# LPF-8-Order.net
KiCad netlist of a schematic drawn in Altium Designer
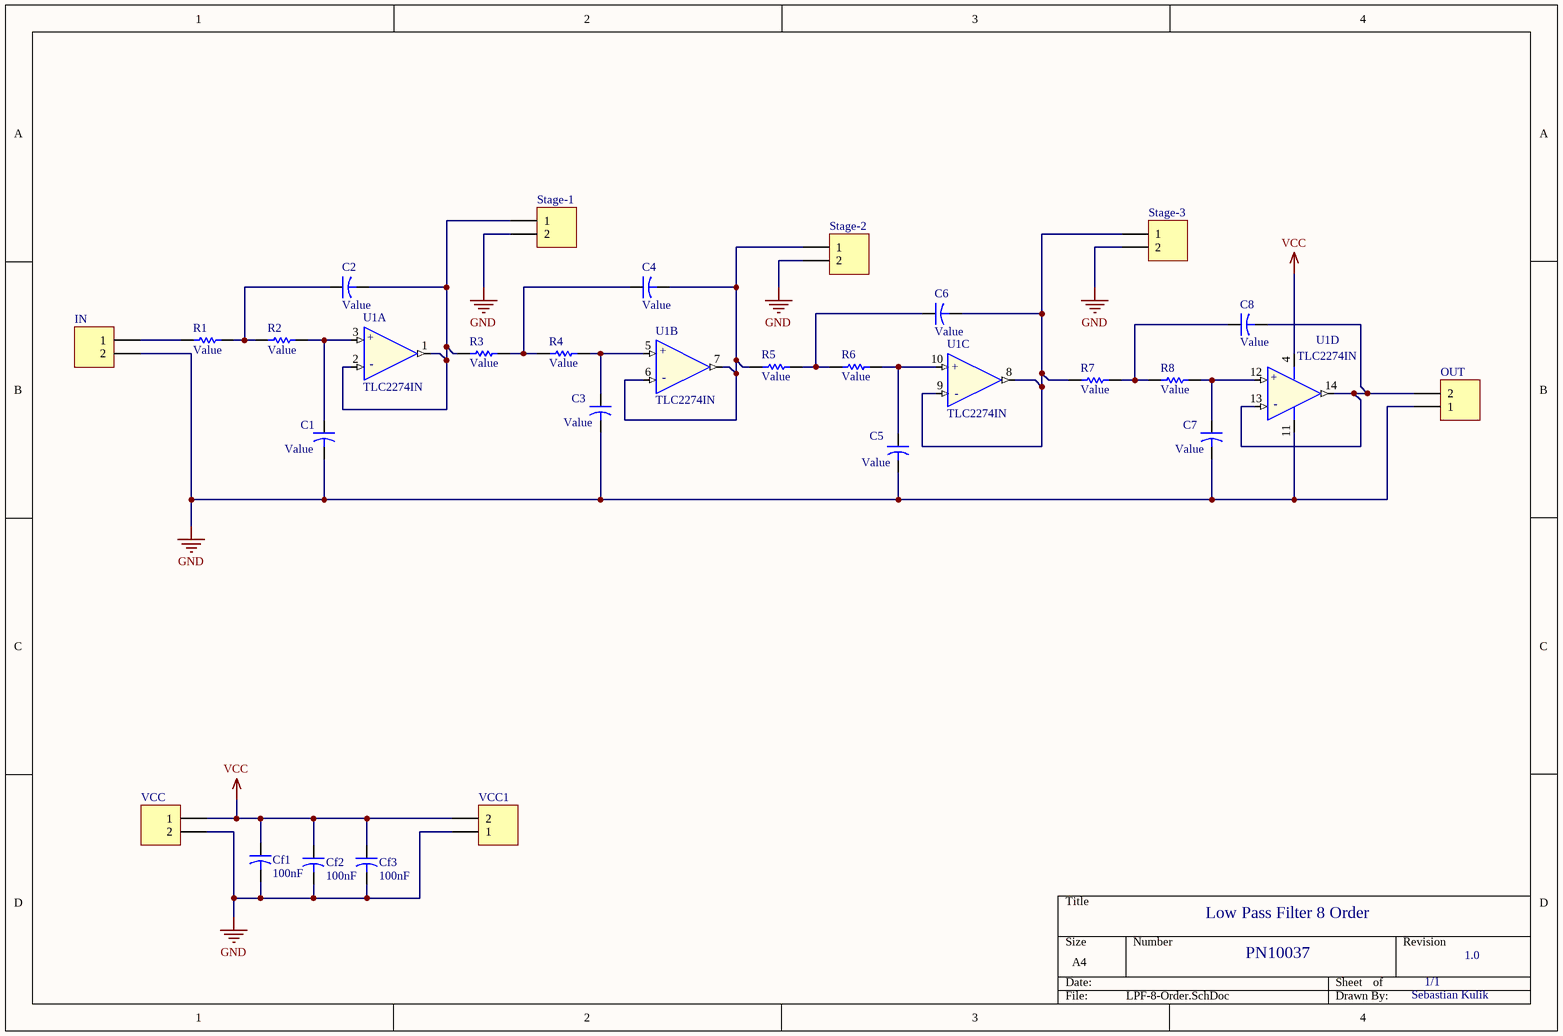
[diagram p0: LPF-8-Order.SchDoc]

(export (version "E")
  (design (tool "Eeschema 10.0.6"))
  (components
    (comp (ref "C1")
      (value "Value")
      (footprint "Dummy-10mm")
      (description "Capacitor-Dummy-THT")
      (fields (field (name "PUBLISHER") "Sebastian Kulik"))
      (libsource (lib "Capacitors") (part "Capacitor-Dummy-THT"))
    )
    (comp (ref "C2")
      (value "Value")
      (footprint "Dummy-10mm")
      (description "Capacitor-Dummy-THT")
      (fields (field (name "PUBLISHER") "Sebastian Kulik"))
      (libsource (lib "Capacitors") (part "Capacitor-Dummy-THT"))
    )
    (comp (ref "C3")
      (value "Value")
      (footprint "Dummy-10mm")
      (description "Capacitor-Dummy-THT")
      (fields (field (name "PUBLISHER") "Sebastian Kulik"))
      (libsource (lib "Capacitors") (part "Capacitor-Dummy-THT"))
    )
    (comp (ref "C4")
      (value "Value")
      (footprint "Dummy-10mm")
      (description "Capacitor-Dummy-THT")
      (fields (field (name "PUBLISHER") "Sebastian Kulik"))
      (libsource (lib "Capacitors") (part "Capacitor-Dummy-THT"))
    )
    (comp (ref "C5")
      (value "Value")
      (footprint "Dummy-10mm")
      (description "Capacitor-Dummy-THT")
      (fields (field (name "PUBLISHER") "Sebastian Kulik"))
      (libsource (lib "Capacitors") (part "Capacitor-Dummy-THT"))
    )
    (comp (ref "C6")
      (value "Value")
      (footprint "Dummy-10mm")
      (description "Capacitor-Dummy-THT")
      (fields (field (name "PUBLISHER") "Sebastian Kulik"))
      (libsource (lib "Capacitors") (part "Capacitor-Dummy-THT"))
    )
    (comp (ref "C7")
      (value "Value")
      (footprint "Dummy-10mm")
      (description "Capacitor-Dummy-THT")
      (fields (field (name "PUBLISHER") "Sebastian Kulik"))
      (libsource (lib "Capacitors") (part "Capacitor-Dummy-THT"))
    )
    (comp (ref "C8")
      (value "Value")
      (footprint "Dummy-10mm")
      (description "Capacitor-Dummy-THT")
      (fields (field (name "PUBLISHER") "Sebastian Kulik"))
      (libsource (lib "Capacitors") (part "Capacitor-Dummy-THT"))
    )
    (comp (ref "Cf1")
      (value "100nF")
      (footprint "Dummy-10mm")
      (description "Capacitor-Dummy-THT")
      (fields (field (name "PUBLISHER") "Sebastian Kulik"))
      (libsource (lib "Capacitors") (part "Capacitor-Dummy-THT"))
    )
    (comp (ref "Cf2")
      (value "100nF")
      (footprint "Dummy-10mm")
      (description "Capacitor-Dummy-THT")
      (fields (field (name "PUBLISHER") "Sebastian Kulik"))
      (libsource (lib "Capacitors") (part "Capacitor-Dummy-THT"))
    )
    (comp (ref "Cf3")
      (value "100nF")
      (footprint "Dummy-10mm")
      (description "Capacitor-Dummy-THT")
      (fields (field (name "PUBLISHER") "Sebastian Kulik"))
      (libsource (lib "Capacitors") (part "Capacitor-Dummy-THT"))
    )
    (comp (ref "IN")
      (value "PHOENIX_1715721")
      (footprint "Phoenix-2-5_08")
      (description "Phoenix, 2 pol, 5.08mm, 22A, 715721")
      (fields (field (name "MANUFACTURER") "Phoenix") (field (name "PUBLISHER") "Sebastian Kulik"))
      (libsource (lib "") (part "2Pol_1715721_1"))
    )
    (comp (ref "OUT")
      (value "PHOENIX_1715721")
      (footprint "Phoenix-2-5_08")
      (description "Phoenix, 2 pol, 5.08mm, 22A, 715721")
      (fields (field (name "MANUFACTURER") "Phoenix") (field (name "PUBLISHER") "Sebastian Kulik"))
      (libsource (lib "Connectors") (part "2Pol_1715721"))
    )
    (comp (ref "R1")
      (value "Value")
      (footprint "Dummy-10mm")
      (description "Resistor-Dummy-THT")
      (fields (field (name "PUBLISHER") "Sebastian Kulik"))
      (libsource (lib "Resistors") (part "Resistor-Dummy-THT"))
    )
    (comp (ref "R2")
      (value "Value")
      (footprint "Dummy-10mm")
      (description "Resistor-Dummy-THT")
      (fields (field (name "PUBLISHER") "Sebastian Kulik"))
      (libsource (lib "Resistors") (part "Resistor-Dummy-THT"))
    )
    (comp (ref "R3")
      (value "Value")
      (footprint "Dummy-10mm")
      (description "Resistor-Dummy-THT")
      (fields (field (name "PUBLISHER") "Sebastian Kulik"))
      (libsource (lib "Resistors") (part "Resistor-Dummy-THT"))
    )
    (comp (ref "R4")
      (value "Value")
      (footprint "Dummy-10mm")
      (description "Resistor-Dummy-THT")
      (fields (field (name "PUBLISHER") "Sebastian Kulik"))
      (libsource (lib "Resistors") (part "Resistor-Dummy-THT"))
    )
    (comp (ref "R5")
      (value "Value")
      (footprint "Dummy-10mm")
      (description "Resistor-Dummy-THT")
      (fields (field (name "PUBLISHER") "Sebastian Kulik"))
      (libsource (lib "Resistors") (part "Resistor-Dummy-THT"))
    )
    (comp (ref "R6")
      (value "Value")
      (footprint "Dummy-10mm")
      (description "Resistor-Dummy-THT")
      (fields (field (name "PUBLISHER") "Sebastian Kulik"))
      (libsource (lib "Resistors") (part "Resistor-Dummy-THT"))
    )
    (comp (ref "R7")
      (value "Value")
      (footprint "Dummy-10mm")
      (description "Resistor-Dummy-THT")
      (fields (field (name "PUBLISHER") "Sebastian Kulik"))
      (libsource (lib "Resistors") (part "Resistor-Dummy-THT"))
    )
    (comp (ref "R8")
      (value "Value")
      (footprint "Dummy-10mm")
      (description "Resistor-Dummy-THT")
      (fields (field (name "PUBLISHER") "Sebastian Kulik"))
      (libsource (lib "Resistors") (part "Resistor-Dummy-THT"))
    )
    (comp (ref "Stage-1")
      (value "Plug_2_90_2.54")
      (footprint "HDR1X2")
      (description "Plug, 2-Pin")
      (fields (field (name "MANUFACTURER") "WE") (field (name "PUBLISHER") "Sebastian Kulik"))
      (libsource (lib "Connectors") (part "Plug_2_90_2.54"))
    )
    (comp (ref "Stage-2")
      (value "Plug_2_90_2.54")
      (footprint "HDR1X2")
      (description "Plug, 2-Pin")
      (fields (field (name "MANUFACTURER") "WE") (field (name "PUBLISHER") "Sebastian Kulik"))
      (libsource (lib "Connectors") (part "Plug_2_90_2.54"))
    )
    (comp (ref "Stage-3")
      (value "Plug_2_90_2.54")
      (footprint "HDR1X2")
      (description "Plug, 2-Pin")
      (fields (field (name "MANUFACTURER") "WE") (field (name "PUBLISHER") "Sebastian Kulik"))
      (libsource (lib "Connectors") (part "Plug_2_90_2.54"))
    )
    (comp (ref "U1")
      (value "TLC2274IN")
      (footprint "DIP-14")
      (description "Reel to Reel  quad OP")
      (fields (field (name "MANUFACTURER") "TI") (field (name "PUBLISHER") "Sebastian Kulik"))
      (libsource (lib "") (part "TLC2274IN_1"))
    )
    (comp (ref "VCC")
      (value "PHOENIX_1715721")
      (footprint "Phoenix-2-5_08")
      (description "Phoenix, 2 pol, 5.08mm, 22A, 715721")
      (fields (field (name "MANUFACTURER") "Phoenix") (field (name "PUBLISHER") "Sebastian Kulik"))
      (libsource (lib "") (part "2Pol_1715721_1"))
    )
    (comp (ref "VCC1")
      (value "PHOENIX_1715721")
      (footprint "Phoenix-2-5_08")
      (description "Phoenix, 2 pol, 5.08mm, 22A, 715721")
      (fields (field (name "MANUFACTURER") "Phoenix") (field (name "PUBLISHER") "Sebastian Kulik"))
      (libsource (lib "Connectors") (part "2Pol_1715721"))
    )
  )
  (nets
    (net (code "1") (name "GND") (class "Default")
      (node (ref "C1") (pin "2") (pinfunction "2_2") (pintype "passive"))
      (node (ref "C3") (pin "2") (pinfunction "2_2") (pintype "passive"))
      (node (ref "C5") (pin "2") (pinfunction "2_2") (pintype "passive"))
      (node (ref "C7") (pin "2") (pinfunction "2_2") (pintype "passive"))
      (node (ref "Cf1") (pin "2") (pinfunction "2_2") (pintype "passive"))
      (node (ref "Cf2") (pin "2") (pinfunction "2_2") (pintype "passive"))
      (node (ref "Cf3") (pin "2") (pinfunction "2_2") (pintype "passive"))
      (node (ref "IN") (pin "2") (pinfunction "2_2") (pintype "passive"))
      (node (ref "OUT") (pin "1") (pinfunction "1_1") (pintype "passive"))
      (node (ref "Stage-1") (pin "2") (pinfunction "2_2") (pintype "passive"))
      (node (ref "Stage-2") (pin "2") (pinfunction "2_2") (pintype "passive"))
      (node (ref "Stage-3") (pin "2") (pinfunction "2_2") (pintype "passive"))
      (node (ref "U1") (pin "11") (pinfunction "V-_11") (pintype "power_in"))
      (node (ref "VCC") (pin "2") (pinfunction "2_2") (pintype "passive"))
      (node (ref "VCC1") (pin "1") (pinfunction "1_1") (pintype "passive"))
    )
    (net (code "2") (name "Net-(C2-Pad1)") (class "Default")
      (node (ref "C2") (pin "1") (pinfunction "1_1") (pintype "passive"))
      (node (ref "R1") (pin "2") (pinfunction "2_2") (pintype "passive"))
      (node (ref "R2") (pin "1") (pinfunction "1_1") (pintype "passive"))
    )
    (net (code "3") (name "Net-(C4-Pad1)") (class "Default")
      (node (ref "C4") (pin "1") (pinfunction "1_1") (pintype "passive"))
      (node (ref "R3") (pin "2") (pinfunction "2_2") (pintype "passive"))
      (node (ref "R4") (pin "1") (pinfunction "1_1") (pintype "passive"))
    )
    (net (code "4") (name "Net-(C6-Pad1)") (class "Default")
      (node (ref "C6") (pin "1") (pinfunction "1_1") (pintype "passive"))
      (node (ref "R5") (pin "2") (pinfunction "2_2") (pintype "passive"))
      (node (ref "R6") (pin "1") (pinfunction "1_1") (pintype "passive"))
    )
    (net (code "5") (name "Net-(C8-Pad1)") (class "Default")
      (node (ref "C8") (pin "1") (pinfunction "1_1") (pintype "passive"))
      (node (ref "R7") (pin "2") (pinfunction "2_2") (pintype "passive"))
      (node (ref "R8") (pin "1") (pinfunction "1_1") (pintype "passive"))
    )
    (net (code "6") (name "Net-(IN-Pad1)") (class "Default")
      (node (ref "IN") (pin "1") (pinfunction "1_1") (pintype "passive"))
      (node (ref "R1") (pin "1") (pinfunction "1_1") (pintype "passive"))
    )
    (net (code "7") (name "Net-(U1A-IN+)") (class "Default")
      (node (ref "C2") (pin "2") (pinfunction "2_2") (pintype "passive"))
      (node (ref "R3") (pin "1") (pinfunction "1_1") (pintype "passive"))
      (node (ref "Stage-1") (pin "1") (pinfunction "1_1") (pintype "passive"))
      (node (ref "U1") (pin "1") (pinfunction "OUT_1") (pintype "output"))
      (node (ref "U1") (pin "2") (pinfunction "IN+_2") (pintype "input"))
    )
    (net (code "8") (name "Net-(U1A-IN-)") (class "Default")
      (node (ref "C1") (pin "1") (pinfunction "1_1") (pintype "passive"))
      (node (ref "R2") (pin "2") (pinfunction "2_2") (pintype "passive"))
      (node (ref "U1") (pin "3") (pinfunction "IN-_3") (pintype "input"))
    )
    (net (code "9") (name "Net-(U1B-IN+)") (class "Default")
      (node (ref "C4") (pin "2") (pinfunction "2_2") (pintype "passive"))
      (node (ref "R5") (pin "1") (pinfunction "1_1") (pintype "passive"))
      (node (ref "Stage-2") (pin "1") (pinfunction "1_1") (pintype "passive"))
      (node (ref "U1") (pin "6") (pinfunction "IN+_6") (pintype "input"))
      (node (ref "U1") (pin "7") (pinfunction "OUT_7") (pintype "output"))
    )
    (net (code "10") (name "Net-(U1B-IN-)") (class "Default")
      (node (ref "C3") (pin "1") (pinfunction "1_1") (pintype "passive"))
      (node (ref "R4") (pin "2") (pinfunction "2_2") (pintype "passive"))
      (node (ref "U1") (pin "5") (pinfunction "IN-_5") (pintype "input"))
    )
    (net (code "11") (name "Net-(U1C-IN+)") (class "Default")
      (node (ref "C6") (pin "2") (pinfunction "2_2") (pintype "passive"))
      (node (ref "R7") (pin "1") (pinfunction "1_1") (pintype "passive"))
      (node (ref "Stage-3") (pin "1") (pinfunction "1_1") (pintype "passive"))
      (node (ref "U1") (pin "8") (pinfunction "OUT_8") (pintype "output"))
      (node (ref "U1") (pin "9") (pinfunction "IN+_9") (pintype "input"))
    )
    (net (code "12") (name "Net-(U1C-IN-)") (class "Default")
      (node (ref "C5") (pin "1") (pinfunction "1_1") (pintype "passive"))
      (node (ref "R6") (pin "2") (pinfunction "2_2") (pintype "passive"))
      (node (ref "U1") (pin "10") (pinfunction "IN-_10") (pintype "input"))
    )
    (net (code "13") (name "Net-(U1D-IN+)") (class "Default")
      (node (ref "C8") (pin "2") (pinfunction "2_2") (pintype "passive"))
      (node (ref "OUT") (pin "2") (pinfunction "2_2") (pintype "passive"))
      (node (ref "U1") (pin "13") (pinfunction "IN+_13") (pintype "input"))
      (node (ref "U1") (pin "14") (pinfunction "OUT_14") (pintype "output"))
    )
    (net (code "14") (name "Net-(U1D-IN-)") (class "Default")
      (node (ref "C7") (pin "1") (pinfunction "1_1") (pintype "passive"))
      (node (ref "R8") (pin "2") (pinfunction "2_2") (pintype "passive"))
      (node (ref "U1") (pin "12") (pinfunction "IN-_12") (pintype "input"))
    )
    (net (code "15") (name "VCC") (class "Default")
      (node (ref "Cf1") (pin "1") (pinfunction "1_1") (pintype "passive"))
      (node (ref "Cf2") (pin "1") (pinfunction "1_1") (pintype "passive"))
      (node (ref "Cf3") (pin "1") (pinfunction "1_1") (pintype "passive"))
      (node (ref "U1") (pin "4") (pinfunction "V+_4") (pintype "power_in"))
      (node (ref "VCC") (pin "1") (pinfunction "1_1") (pintype "passive"))
      (node (ref "VCC1") (pin "2") (pinfunction "2_2") (pintype "passive"))
    )
  )
)
